# Sheet1_Codec.net
KiCad netlist of a schematic drawn in Altium Designer
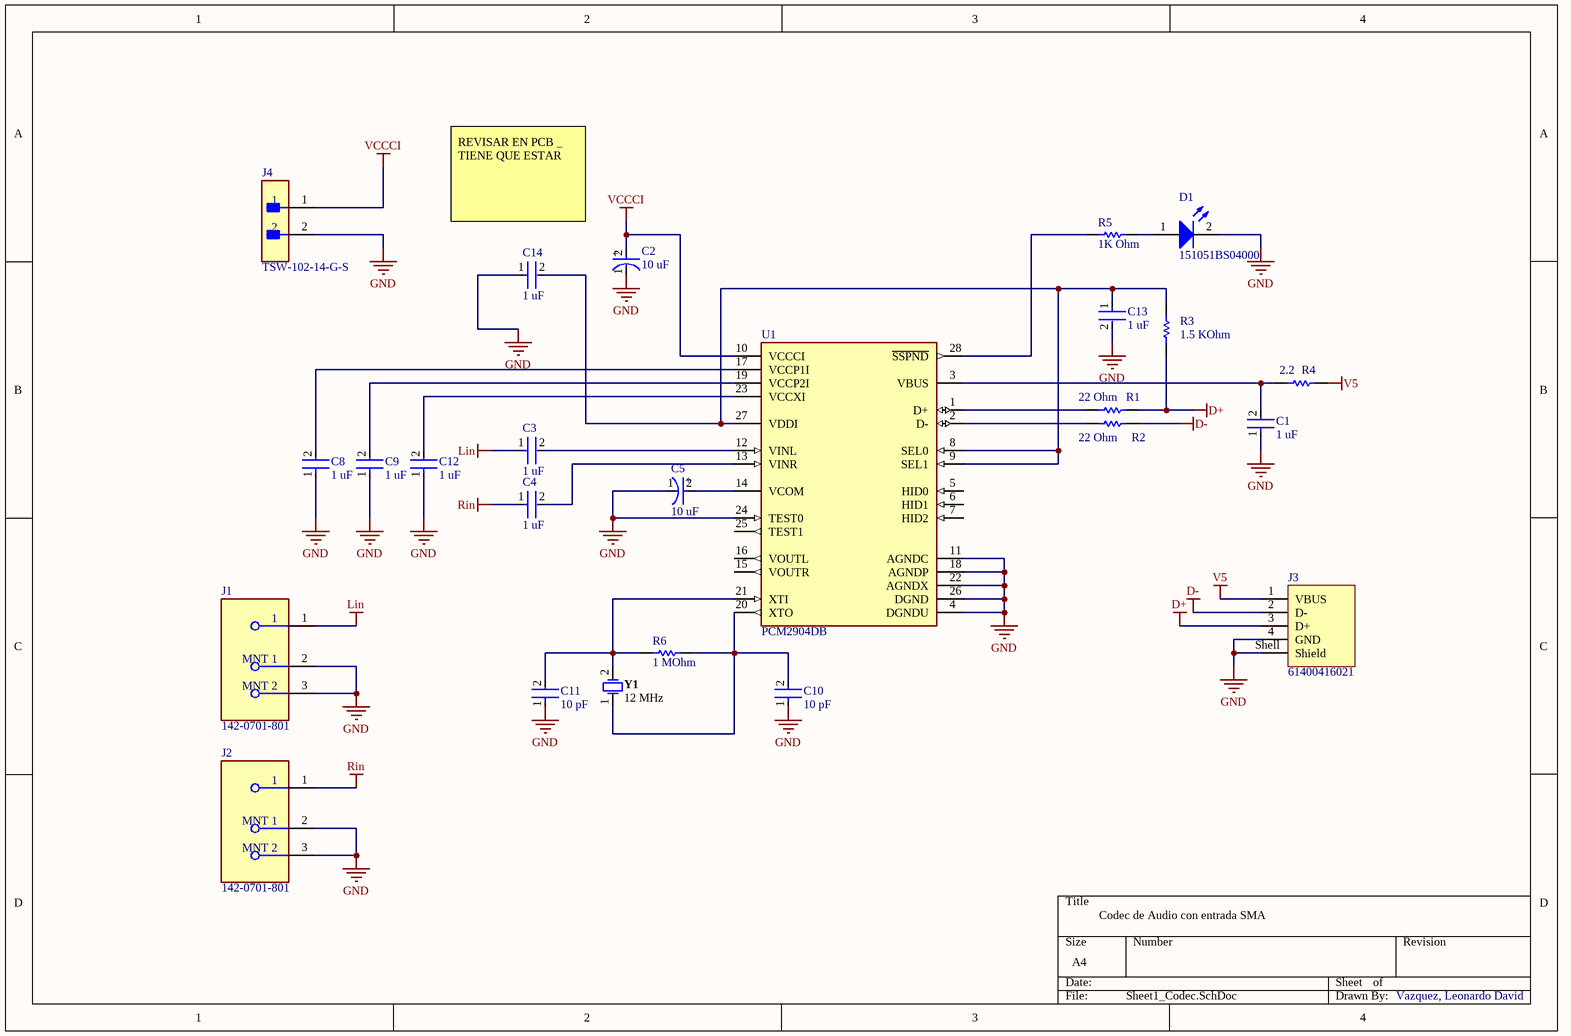
[diagram p0: Sheet1_Codec.SchDoc]

(export (version "E")
  (design (tool "Eeschema 10.0.6"))
  (components
    (comp (ref "C1")
      (value "1 uF")
      (footprint "FP-CC0805-0_85-MFG")
      (description "CAP CER 0.1UF 50V X7R 0805")
      (fields (field (name "TOLERANCE") "0.1") (field (name "MANUFACTURER PART NUMBER") "CC0805KRX7R9BB104"))
      (libsource (lib "Altium Content Vault") (part "11868f565c42a9108669ba33697ecf6"))
    )
    (comp (ref "C2")
      (value "10 uF")
      (footprint "FP-RAD-TH-D_6_3_0_5-L_7_1-MFG")
      (description "Aluminum Electrolytic Capacitors (Radial Lead Type) 100uF ±20% 16V")
      (fields (field (name "VOLTAGE") "16V") (field (name "TOLERANCE") "20%"))
      (libsource (lib "Altium Content Vault") (part "a00bbbee19879c290e62620ae7e47b1"))
    )
    (comp (ref "C3")
      (value "1 uF")
      (footprint "FP-CC0805-0_85-MFG")
      (description "CAP CER 0.1UF 50V X7R 0805")
      (fields (field (name "TOLERANCE") "0.1") (field (name "MANUFACTURER PART NUMBER") "CC0805KRX7R9BB104"))
      (libsource (lib "Altium Content Vault") (part "11868f565c42a9108669ba33697ecf6"))
    )
    (comp (ref "C4")
      (value "1 uF")
      (footprint "FP-CC0805-0_85-MFG")
      (description "CAP CER 0.1UF 50V X7R 0805")
      (fields (field (name "TOLERANCE") "0.1") (field (name "MANUFACTURER PART NUMBER") "CC0805KRX7R9BB104"))
      (libsource (lib "Altium Content Vault") (part "11868f565c42a9108669ba33697ecf6"))
    )
    (comp (ref "C5")
      (value "10 uF")
      (footprint "FP-RAD-TH-D_6_3_0_5-L_7_1-MFG")
      (description "Aluminum Electrolytic Capacitors (Radial Lead Type) 100uF ±20% 16V")
      (fields (field (name "VOLTAGE") "16V") (field (name "TOLERANCE") "20%"))
      (libsource (lib "Altium Content Vault") (part "a00bbbee19879c290e62620ae7e47b1"))
    )
    (comp (ref "C8")
      (value "1 uF")
      (footprint "FP-CC0805-0_85-MFG")
      (description "CAP CER 0.1UF 50V X7R 0805")
      (fields (field (name "TOLERANCE") "0.1") (field (name "MANUFACTURER PART NUMBER") "CC0805KRX7R9BB104"))
      (libsource (lib "Altium Content Vault") (part "11868f565c42a9108669ba33697ecf6"))
    )
    (comp (ref "C9")
      (value "1 uF")
      (footprint "FP-CC0805-0_85-MFG")
      (description "CAP CER 0.1UF 50V X7R 0805")
      (fields (field (name "TOLERANCE") "0.1") (field (name "MANUFACTURER PART NUMBER") "CC0805KRX7R9BB104"))
      (libsource (lib "Altium Content Vault") (part "11868f565c42a9108669ba33697ecf6"))
    )
    (comp (ref "C10")
      (value "10 pF")
      (footprint "FP-CC0805-0_85-MFG")
      (description "CAP CER 0.1UF 50V X7R 0805")
      (fields (field (name "TOLERANCE") "0.1") (field (name "MANUFACTURER PART NUMBER") "CC0805KRX7R9BB104"))
      (libsource (lib "Altium Content Vault") (part "11868f565c42a9108669ba33697ecf6"))
    )
    (comp (ref "C11")
      (value "10 pF")
      (footprint "FP-CC0805-0_85-MFG")
      (description "CAP CER 0.1UF 50V X7R 0805")
      (fields (field (name "TOLERANCE") "0.1") (field (name "MANUFACTURER PART NUMBER") "CC0805KRX7R9BB104"))
      (libsource (lib "Altium Content Vault") (part "11868f565c42a9108669ba33697ecf6"))
    )
    (comp (ref "C12")
      (value "1 uF")
      (footprint "FP-CC0805-0_85-MFG")
      (description "CAP CER 0.1UF 50V X7R 0805")
      (fields (field (name "TOLERANCE") "0.1") (field (name "MANUFACTURER PART NUMBER") "CC0805KRX7R9BB104"))
      (libsource (lib "Altium Content Vault") (part "11868f565c42a9108669ba33697ecf6"))
    )
    (comp (ref "C13")
      (value "1 uF")
      (footprint "FP-CC0805-0_85-MFG")
      (description "CAP CER 0.1UF 50V X7R 0805")
      (fields (field (name "TOLERANCE") "0.1") (field (name "MANUFACTURER PART NUMBER") "CC0805KRX7R9BB104"))
      (libsource (lib "Altium Content Vault") (part "11868f565c42a9108669ba33697ecf6"))
    )
    (comp (ref "C14")
      (value "1 uF")
      (footprint "FP-CC0805-0_85-MFG")
      (description "CAP CER 0.1UF 50V X7R 0805")
      (fields (field (name "TOLERANCE") "0.1") (field (name "MANUFACTURER PART NUMBER") "CC0805KRX7R9BB104"))
      (libsource (lib "Altium Content Vault") (part "11868f565c42a9108669ba33697ecf6"))
    )
    (comp (ref "D1")
      (value "151051BS04000")
      (footprint "WL-TMRC_D5.9H8.7")
      (libsource (lib "Altium Content Vault") (part "LED_Blue_1A-2K"))
    )
    (comp (ref "J1")
      (value "142-0701-801")
      (footprint "FP-142-0701-801-MFG")
      (description "CONN SMA JACK STR 50OHM EDGE MNT")
      (libsource (lib "Altium Content Vault") (part "89929399afe843c8b6880c6cbd0f99a"))
    )
    (comp (ref "J2")
      (value "142-0701-801")
      (footprint "FP-142-0701-801-MFG")
      (description "CONN SMA JACK STR 50OHM EDGE MNT")
      (libsource (lib "Altium Content Vault") (part "89929399afe843c8b6880c6cbd0f99a"))
    )
    (comp (ref "J3")
      (value "61400416021")
      (footprint "61400416021")
      (libsource (lib "Altium Content Vault") (part "USB 2.0_Type A_Receptacle_1 Port"))
    )
    (comp (ref "J4")
      (value "TSW-102-14-G-S")
      (footprint "FP-TSW-102-14-G-S-MFG")
      (description "CONN HEADER VERT 2POS 2.54MM")
      (libsource (lib "Altium Content Vault") (part "88c1139f9d239099ffebecbe3f7647a"))
    )
    (comp (ref "R1")
      (value "22 Ohm")
      (footprint "RESC2013X60X40ML20T25")
      (fields (field (name "MANUFACTURER") "Panasonic") (field (name "PART NUMBER") "ERA6AEB101V"))
      (libsource (lib "Altium Content Vault") (part "RES"))
    )
    (comp (ref "R2")
      (value "22 Ohm")
      (footprint "RESC2013X60X40ML20T25")
      (fields (field (name "MANUFACTURER") "Panasonic") (field (name "PART NUMBER") "ERA6AEB101V"))
      (libsource (lib "Altium Content Vault") (part "RES"))
    )
    (comp (ref "R3")
      (value "1.5 KOhm")
      (footprint "RESC2013X60X40ML20T25")
      (fields (field (name "MANUFACTURER") "Panasonic") (field (name "PART NUMBER") "ERA6AEB101V"))
      (libsource (lib "Altium Content Vault") (part "RES"))
    )
    (comp (ref "R4")
      (value "2.2")
      (footprint "RESC2013X60X40ML20T25")
      (fields (field (name "MANUFACTURER") "Panasonic") (field (name "PART NUMBER") "ERA6AEB101V"))
      (libsource (lib "Altium Content Vault") (part "RES"))
    )
    (comp (ref "R5")
      (value "1K Ohm")
      (footprint "RESC2013X60X40ML20T25")
      (fields (field (name "MANUFACTURER") "Panasonic") (field (name "PART NUMBER") "ERA6AEB101V"))
      (libsource (lib "Altium Content Vault") (part "RES"))
    )
    (comp (ref "R6")
      (value "1 MOhm")
      (footprint "RESC2013X60X40ML20T25")
      (fields (field (name "MANUFACTURER") "Panasonic") (field (name "PART NUMBER") "ERA6AEB101V"))
      (libsource (lib "Altium Content Vault") (part "RES"))
    )
    (comp (ref "U1")
      (value "PCM2904DB")
      (footprint "FP-DB0028A-IPC_A")
      (description "IC STEREO AUD CODEC W/USB 28SSOP")
      (libsource (lib "Altium Content Vault") (part "e359a79613c207c48d96439f04dff7f"))
    )
    (comp (ref "Y1")
      (value "12 MHz")
      (footprint "FOX-FOXSLF160-20")
      (description "Resistance Weld Thru-Hole Crystal, 16 MHz, -20 to 70 degC, 2-Pin THD, RoHS, Bulk")
      (fields (field (name "TOLERANCE") "1%"))
      (libsource (lib "Altium Content Vault") (part "XTAL-1-2-2"))
    )
  )
  (nets
    (net (code "1") (name "D+") (class "Default")
      (node (ref "J3") (pin "3") (pinfunction "D+_3") (pintype "passive"))
      (node (ref "R1") (pin "1") (pinfunction "1_1") (pintype "passive"))
      (node (ref "R3") (pin "2") (pinfunction "2_2") (pintype "passive"))
    )
    (net (code "2") (name "D-") (class "Default")
      (node (ref "J3") (pin "2") (pinfunction "D-_2") (pintype "passive"))
      (node (ref "R2") (pin "2") (pinfunction "2_2") (pintype "passive"))
    )
    (net (code "3") (name "GND") (class "Default")
      (node (ref "C1") (pin "1") (pinfunction "1_1") (pintype "passive"))
      (node (ref "C10") (pin "1") (pinfunction "1_1") (pintype "passive"))
      (node (ref "C11") (pin "1") (pinfunction "1_1") (pintype "passive"))
      (node (ref "C12") (pin "1") (pinfunction "1_1") (pintype "passive"))
      (node (ref "C13") (pin "2") (pinfunction "2_2") (pintype "passive"))
      (node (ref "C14") (pin "1") (pinfunction "1_1") (pintype "passive"))
      (node (ref "C2") (pin "1") (pinfunction "C_1") (pintype "passive"))
      (node (ref "C5") (pin "1") (pinfunction "C_1") (pintype "passive"))
      (node (ref "C8") (pin "1") (pinfunction "1_1") (pintype "passive"))
      (node (ref "C9") (pin "1") (pinfunction "1_1") (pintype "passive"))
      (node (ref "D1") (pin "2") (pinfunction "K_2") (pintype "passive"))
      (node (ref "J1") (pin "2") (pinfunction "MNT_1_2") (pintype "passive"))
      (node (ref "J1") (pin "3") (pinfunction "MNT_2_3") (pintype "passive"))
      (node (ref "J2") (pin "2") (pinfunction "MNT_1_2") (pintype "passive"))
      (node (ref "J2") (pin "3") (pinfunction "MNT_2_3") (pintype "passive"))
      (node (ref "J3") (pin "4") (pinfunction "GND_4") (pintype "passive"))
      (node (ref "J3") (pin "Shell") (pinfunction "Shield_Shell") (pintype "passive"))
      (node (ref "J4") (pin "2") (pinfunction "2_2") (pintype "passive"))
      (node (ref "U1") (pin "11") (pinfunction "AGNDC_11") (pintype "power_in"))
      (node (ref "U1") (pin "18") (pinfunction "AGNDP_18") (pintype "power_in"))
      (node (ref "U1") (pin "22") (pinfunction "AGNDX_22") (pintype "power_in"))
      (node (ref "U1") (pin "24") (pinfunction "TEST0_24") (pintype "input"))
      (node (ref "U1") (pin "26") (pinfunction "DGND_26") (pintype "power_in"))
      (node (ref "U1") (pin "4") (pinfunction "DGNDU_4") (pintype "power_in"))
    )
    (net (code "4") (name "Lin") (class "Default")
      (node (ref "C3") (pin "1") (pinfunction "1_1") (pintype "passive"))
      (node (ref "J1") (pin "1") (pinfunction "1_1") (pintype "passive"))
    )
    (net (code "5") (name "Net-(C5-A)") (class "Default")
      (node (ref "C5") (pin "2") (pinfunction "A_2") (pintype "passive"))
      (node (ref "U1") (pin "14") (pinfunction "VCOM_14") (pintype "power_in"))
    )
    (net (code "6") (name "Net-(D1-A)") (class "Default")
      (node (ref "D1") (pin "1") (pinfunction "A_1") (pintype "passive"))
      (node (ref "R5") (pin "1") (pinfunction "1_1") (pintype "passive"))
    )
    (net (code "7") (name "Net-(U1-D+)") (class "Default")
      (node (ref "R1") (pin "2") (pinfunction "2_2") (pintype "passive"))
      (node (ref "U1") (pin "1") (pinfunction "D+_1") (pintype "bidirectional"))
    )
    (net (code "8") (name "Net-(U1-D-)") (class "Default")
      (node (ref "R2") (pin "1") (pinfunction "1_1") (pintype "passive"))
      (node (ref "U1") (pin "2") (pinfunction "D-_2") (pintype "bidirectional"))
    )
    (net (code "9") (name "Net-(U1-SEL0)") (class "Default")
      (node (ref "C13") (pin "1") (pinfunction "1_1") (pintype "passive"))
      (node (ref "C14") (pin "2") (pinfunction "2_2") (pintype "passive"))
      (node (ref "R3") (pin "1") (pinfunction "1_1") (pintype "passive"))
      (node (ref "U1") (pin "27") (pinfunction "VDDI_27") (pintype "power_in"))
      (node (ref "U1") (pin "8") (pinfunction "SEL0_8") (pintype "input"))
      (node (ref "U1") (pin "9") (pinfunction "SEL1_9") (pintype "input"))
    )
    (net (code "10") (name "Net-(U1-VBUS)") (class "Default")
      (node (ref "C1") (pin "2") (pinfunction "2_2") (pintype "passive"))
      (node (ref "R4") (pin "2") (pinfunction "2_2") (pintype "passive"))
      (node (ref "U1") (pin "3") (pinfunction "VBUS_3") (pintype "power_in"))
    )
    (net (code "11") (name "Net-(U1-VCCP1I)") (class "Default")
      (node (ref "C8") (pin "2") (pinfunction "2_2") (pintype "passive"))
      (node (ref "U1") (pin "17") (pinfunction "VCCP1I_17") (pintype "power_in"))
    )
    (net (code "12") (name "Net-(U1-VCCP2I)") (class "Default")
      (node (ref "C9") (pin "2") (pinfunction "2_2") (pintype "passive"))
      (node (ref "U1") (pin "19") (pinfunction "VCCP2I_19") (pintype "power_in"))
    )
    (net (code "13") (name "Net-(U1-VCCXI)") (class "Default")
      (node (ref "C12") (pin "2") (pinfunction "2_2") (pintype "passive"))
      (node (ref "U1") (pin "23") (pinfunction "VCCXI_23") (pintype "power_in"))
    )
    (net (code "14") (name "Net-(U1-VINL)") (class "Default")
      (node (ref "C3") (pin "2") (pinfunction "2_2") (pintype "passive"))
      (node (ref "U1") (pin "12") (pinfunction "VINL_12") (pintype "input"))
    )
    (net (code "15") (name "Net-(U1-VINR)") (class "Default")
      (node (ref "C4") (pin "2") (pinfunction "2_2") (pintype "passive"))
      (node (ref "U1") (pin "13") (pinfunction "VINR_13") (pintype "input"))
    )
    (net (code "16") (name "Net-(U1-XTI)") (class "Default")
      (node (ref "C11") (pin "2") (pinfunction "2_2") (pintype "passive"))
      (node (ref "R6") (pin "1") (pinfunction "1_1") (pintype "passive"))
      (node (ref "U1") (pin "21") (pinfunction "XTI_21") (pintype "input"))
      (node (ref "Y1") (pin "2") (pinfunction "2_2") (pintype "passive"))
    )
    (net (code "17") (name "Net-(U1-XTO)") (class "Default")
      (node (ref "C10") (pin "2") (pinfunction "2_2") (pintype "passive"))
      (node (ref "R6") (pin "2") (pinfunction "2_2") (pintype "passive"))
      (node (ref "U1") (pin "20") (pinfunction "XTO_20") (pintype "output"))
      (node (ref "Y1") (pin "1") (pinfunction "1_1") (pintype "passive"))
    )
    (net (code "18") (name "Net-(U1-~{SSPND})") (class "Default")
      (node (ref "R5") (pin "2") (pinfunction "2_2") (pintype "passive"))
      (node (ref "U1") (pin "28") (pinfunction "~{SSPND}_28") (pintype "output"))
    )
    (net (code "19") (name "Rin") (class "Default")
      (node (ref "C4") (pin "1") (pinfunction "1_1") (pintype "passive"))
      (node (ref "J2") (pin "1") (pinfunction "1_1") (pintype "passive"))
    )
    (net (code "20") (name "V5") (class "Default")
      (node (ref "J3") (pin "1") (pinfunction "VBUS_1") (pintype "passive"))
      (node (ref "R4") (pin "1") (pinfunction "1_1") (pintype "passive"))
    )
    (net (code "21") (name "VCCCI") (class "Default")
      (node (ref "C2") (pin "2") (pinfunction "A_2") (pintype "passive"))
      (node (ref "J4") (pin "1") (pinfunction "1_1") (pintype "passive"))
      (node (ref "U1") (pin "10") (pinfunction "VCCCI_10") (pintype "power_in"))
    )
    (net (code "22") (name "unconnected-(U1-HID0-Pad5)") (class "Default")
      (node (ref "U1") (pin "5") (pinfunction "HID0_5") (pintype "input"))
    )
    (net (code "23") (name "unconnected-(U1-HID1-Pad6)") (class "Default")
      (node (ref "U1") (pin "6") (pinfunction "HID1_6") (pintype "input"))
    )
    (net (code "24") (name "unconnected-(U1-HID2-Pad7)") (class "Default")
      (node (ref "U1") (pin "7") (pinfunction "HID2_7") (pintype "input"))
    )
    (net (code "25") (name "unconnected-(U1-TEST1-Pad25)") (class "Default")
      (node (ref "U1") (pin "25") (pinfunction "TEST1_25") (pintype "output"))
    )
    (net (code "26") (name "unconnected-(U1-VOUTL-Pad16)") (class "Default")
      (node (ref "U1") (pin "16") (pinfunction "VOUTL_16") (pintype "output"))
    )
    (net (code "27") (name "unconnected-(U1-VOUTR-Pad15)") (class "Default")
      (node (ref "U1") (pin "15") (pinfunction "VOUTR_15") (pintype "output"))
    )
  )
)
